# pantalla.net
KiCad netlist of a schematic drawn in EAGLE
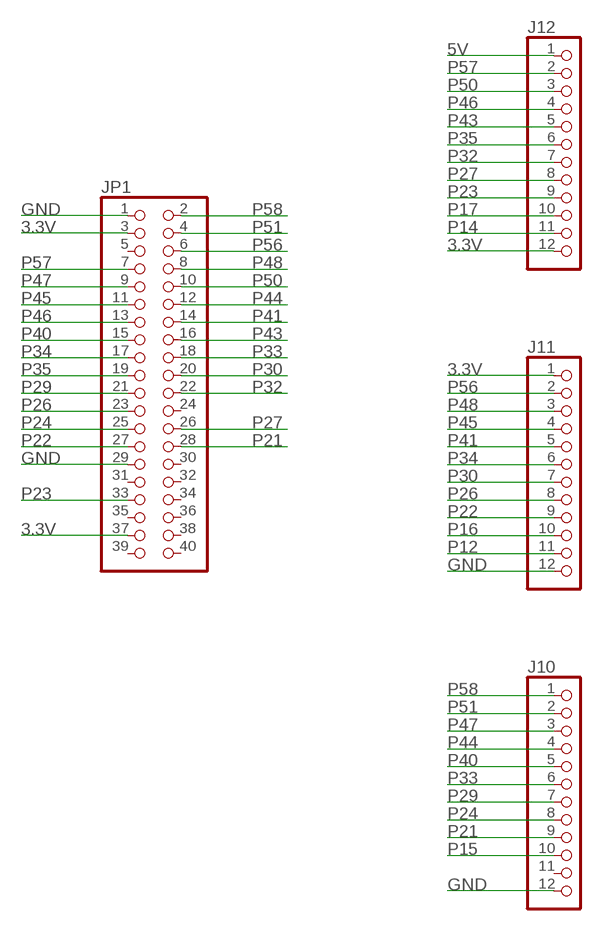
[diagram p0: schematic, sheet 1]

(export (version "E")
  (design (tool "Eeschema 10.0.6"))
  (components
    (comp (ref "J10")
      (value "PINHD-1X12")
      (footprint "eagle-import:1X12")
      (libsource (lib "eagle-import") (part "PINHD-1X12"))
    )
    (comp (ref "J11")
      (value "PINHD-1X12")
      (footprint "eagle-import:1X12")
      (libsource (lib "eagle-import") (part "PINHD-1X12"))
    )
    (comp (ref "J12")
      (value "PINHD-1X12")
      (footprint "eagle-import:1X12")
      (libsource (lib "eagle-import") (part "PINHD-1X12"))
    )
    (comp (ref "JP1")
      (value "PINHD-2X20")
      (footprint "eagle-import:2X20")
      (libsource (lib "eagle-import") (part "PINHD-2X20"))
    )
  )
  (nets
    (net (code "1") (name "/3.3V") (class "Default")
      (node (ref "J11") (pin "1") (pinfunction "1_1") (pintype "passive"))
      (node (ref "J12") (pin "12") (pinfunction "12_12") (pintype "passive"))
      (node (ref "JP1") (pin "3") (pinfunction "3_3") (pintype "passive"))
      (node (ref "JP1") (pin "37") (pinfunction "37_37") (pintype "passive"))
    )
    (net (code "2") (name "/5V") (class "Default")
      (node (ref "J12") (pin "1") (pinfunction "1_1") (pintype "passive"))
    )
    (net (code "3") (name "/GND") (class "Default")
      (node (ref "J10") (pin "12") (pinfunction "12_12") (pintype "passive"))
      (node (ref "J11") (pin "12") (pinfunction "12_12") (pintype "passive"))
      (node (ref "JP1") (pin "1") (pinfunction "1_1") (pintype "passive"))
      (node (ref "JP1") (pin "29") (pinfunction "29_29") (pintype "passive"))
    )
    (net (code "4") (name "/P12") (class "Default")
      (node (ref "J11") (pin "11") (pinfunction "11_11") (pintype "passive"))
    )
    (net (code "5") (name "/P14") (class "Default")
      (node (ref "J12") (pin "11") (pinfunction "11_11") (pintype "passive"))
    )
    (net (code "6") (name "/P15") (class "Default")
      (node (ref "J10") (pin "10") (pinfunction "10_10") (pintype "passive"))
    )
    (net (code "7") (name "/P16") (class "Default")
      (node (ref "J11") (pin "10") (pinfunction "10_10") (pintype "passive"))
    )
    (net (code "8") (name "/P17") (class "Default")
      (node (ref "J12") (pin "10") (pinfunction "10_10") (pintype "passive"))
    )
    (net (code "9") (name "/P21") (class "Default")
      (node (ref "J10") (pin "9") (pinfunction "9_9") (pintype "passive"))
      (node (ref "JP1") (pin "28") (pinfunction "28_28") (pintype "passive"))
    )
    (net (code "10") (name "/P22") (class "Default")
      (node (ref "J11") (pin "9") (pinfunction "9_9") (pintype "passive"))
      (node (ref "JP1") (pin "27") (pinfunction "27_27") (pintype "passive"))
    )
    (net (code "11") (name "/P23") (class "Default")
      (node (ref "J12") (pin "9") (pinfunction "9_9") (pintype "passive"))
      (node (ref "JP1") (pin "33") (pinfunction "33_33") (pintype "passive"))
    )
    (net (code "12") (name "/P24") (class "Default")
      (node (ref "J10") (pin "8") (pinfunction "8_8") (pintype "passive"))
      (node (ref "JP1") (pin "25") (pinfunction "25_25") (pintype "passive"))
    )
    (net (code "13") (name "/P26") (class "Default")
      (node (ref "J11") (pin "8") (pinfunction "8_8") (pintype "passive"))
      (node (ref "JP1") (pin "23") (pinfunction "23_23") (pintype "passive"))
    )
    (net (code "14") (name "/P27") (class "Default")
      (node (ref "J12") (pin "8") (pinfunction "8_8") (pintype "passive"))
      (node (ref "JP1") (pin "26") (pinfunction "26_26") (pintype "passive"))
    )
    (net (code "15") (name "/P29") (class "Default")
      (node (ref "J10") (pin "7") (pinfunction "7_7") (pintype "passive"))
      (node (ref "JP1") (pin "21") (pinfunction "21_21") (pintype "passive"))
    )
    (net (code "16") (name "/P30") (class "Default")
      (node (ref "J11") (pin "7") (pinfunction "7_7") (pintype "passive"))
      (node (ref "JP1") (pin "20") (pinfunction "20_20") (pintype "passive"))
    )
    (net (code "17") (name "/P32") (class "Default")
      (node (ref "J12") (pin "7") (pinfunction "7_7") (pintype "passive"))
      (node (ref "JP1") (pin "22") (pinfunction "22_22") (pintype "passive"))
    )
    (net (code "18") (name "/P33") (class "Default")
      (node (ref "J10") (pin "6") (pinfunction "6_6") (pintype "passive"))
      (node (ref "JP1") (pin "18") (pinfunction "18_18") (pintype "passive"))
    )
    (net (code "19") (name "/P34") (class "Default")
      (node (ref "J11") (pin "6") (pinfunction "6_6") (pintype "passive"))
      (node (ref "JP1") (pin "17") (pinfunction "17_17") (pintype "passive"))
    )
    (net (code "20") (name "/P35") (class "Default")
      (node (ref "J12") (pin "6") (pinfunction "6_6") (pintype "passive"))
      (node (ref "JP1") (pin "19") (pinfunction "19_19") (pintype "passive"))
    )
    (net (code "21") (name "/P40") (class "Default")
      (node (ref "J10") (pin "5") (pinfunction "5_5") (pintype "passive"))
      (node (ref "JP1") (pin "15") (pinfunction "15_15") (pintype "passive"))
    )
    (net (code "22") (name "/P41") (class "Default")
      (node (ref "J11") (pin "5") (pinfunction "5_5") (pintype "passive"))
      (node (ref "JP1") (pin "14") (pinfunction "14_14") (pintype "passive"))
    )
    (net (code "23") (name "/P43") (class "Default")
      (node (ref "J12") (pin "5") (pinfunction "5_5") (pintype "passive"))
      (node (ref "JP1") (pin "16") (pinfunction "16_16") (pintype "passive"))
    )
    (net (code "24") (name "/P44") (class "Default")
      (node (ref "J10") (pin "4") (pinfunction "4_4") (pintype "passive"))
      (node (ref "JP1") (pin "12") (pinfunction "12_12") (pintype "passive"))
    )
    (net (code "25") (name "/P45") (class "Default")
      (node (ref "J11") (pin "4") (pinfunction "4_4") (pintype "passive"))
      (node (ref "JP1") (pin "11") (pinfunction "11_11") (pintype "passive"))
    )
    (net (code "26") (name "/P46") (class "Default")
      (node (ref "J12") (pin "4") (pinfunction "4_4") (pintype "passive"))
      (node (ref "JP1") (pin "13") (pinfunction "13_13") (pintype "passive"))
    )
    (net (code "27") (name "/P47") (class "Default")
      (node (ref "J10") (pin "3") (pinfunction "3_3") (pintype "passive"))
      (node (ref "JP1") (pin "9") (pinfunction "9_9") (pintype "passive"))
    )
    (net (code "28") (name "/P48") (class "Default")
      (node (ref "J11") (pin "3") (pinfunction "3_3") (pintype "passive"))
      (node (ref "JP1") (pin "8") (pinfunction "8_8") (pintype "passive"))
    )
    (net (code "29") (name "/P50") (class "Default")
      (node (ref "J12") (pin "3") (pinfunction "3_3") (pintype "passive"))
      (node (ref "JP1") (pin "10") (pinfunction "10_10") (pintype "passive"))
    )
    (net (code "30") (name "/P51") (class "Default")
      (node (ref "J10") (pin "2") (pinfunction "2_2") (pintype "passive"))
      (node (ref "JP1") (pin "4") (pinfunction "4_4") (pintype "passive"))
    )
    (net (code "31") (name "/P56") (class "Default")
      (node (ref "J11") (pin "2") (pinfunction "2_2") (pintype "passive"))
      (node (ref "JP1") (pin "6") (pinfunction "6_6") (pintype "passive"))
    )
    (net (code "32") (name "/P57") (class "Default")
      (node (ref "J12") (pin "2") (pinfunction "2_2") (pintype "passive"))
      (node (ref "JP1") (pin "7") (pinfunction "7_7") (pintype "passive"))
    )
    (net (code "33") (name "/P58") (class "Default")
      (node (ref "J10") (pin "1") (pinfunction "1_1") (pintype "passive"))
      (node (ref "JP1") (pin "2") (pinfunction "2_2") (pintype "passive"))
    )
    (net (code "34") (name "unconnected-(J10-Pad11)") (class "Default")
      (node (ref "J10") (pin "11") (pinfunction "11_11") (pintype "passive"))
    )
    (net (code "35") (name "unconnected-(JP1-Pad5)") (class "Default")
      (node (ref "JP1") (pin "5") (pinfunction "5_5") (pintype "passive"))
    )
    (net (code "36") (name "unconnected-(JP1-Pad24)") (class "Default")
      (node (ref "JP1") (pin "24") (pinfunction "24_24") (pintype "passive"))
    )
    (net (code "37") (name "unconnected-(JP1-Pad30)") (class "Default")
      (node (ref "JP1") (pin "30") (pinfunction "30_30") (pintype "passive"))
    )
    (net (code "38") (name "unconnected-(JP1-Pad31)") (class "Default")
      (node (ref "JP1") (pin "31") (pinfunction "31_31") (pintype "passive"))
    )
    (net (code "39") (name "unconnected-(JP1-Pad32)") (class "Default")
      (node (ref "JP1") (pin "32") (pinfunction "32_32") (pintype "passive"))
    )
    (net (code "40") (name "unconnected-(JP1-Pad34)") (class "Default")
      (node (ref "JP1") (pin "34") (pinfunction "34_34") (pintype "passive"))
    )
    (net (code "41") (name "unconnected-(JP1-Pad35)") (class "Default")
      (node (ref "JP1") (pin "35") (pinfunction "35_35") (pintype "passive"))
    )
    (net (code "42") (name "unconnected-(JP1-Pad36)") (class "Default")
      (node (ref "JP1") (pin "36") (pinfunction "36_36") (pintype "passive"))
    )
    (net (code "43") (name "unconnected-(JP1-Pad38)") (class "Default")
      (node (ref "JP1") (pin "38") (pinfunction "38_38") (pintype "passive"))
    )
    (net (code "44") (name "unconnected-(JP1-Pad39)") (class "Default")
      (node (ref "JP1") (pin "39") (pinfunction "39_39") (pintype "passive"))
    )
    (net (code "45") (name "unconnected-(JP1-Pad40)") (class "Default")
      (node (ref "JP1") (pin "40") (pinfunction "40_40") (pintype "passive"))
    )
  )
)
